# RpiOnOff.net
KiCad netlist of a schematic drawn in EAGLE
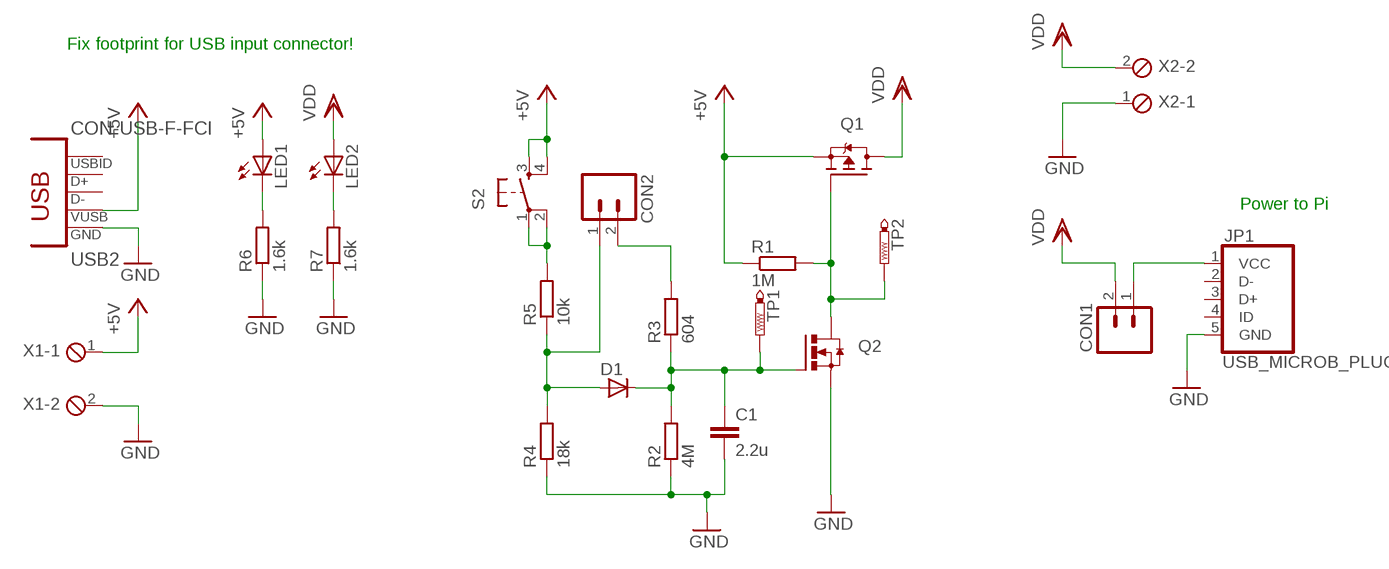
[diagram p0: schematic, sheet 1]

(export (version "E")
  (design (tool "Eeschema 10.0.6"))
  (components
    (comp (ref "C1")
      (value "2.2u")
      (footprint "eagle-import:C0603")
      (libsource (lib "eagle-import") (part "C-EUC0603"))
    )
    (comp (ref "CON1")
      (value "CONNECTOR-1X2[2.54MM]")
      (footprint "eagle-import:CONNECTOR-1X2-2.54MM")
      (libsource (lib "eagle-import") (part "CONNECTOR-1X2[2.54MM]"))
    )
    (comp (ref "CON2")
      (value "CONNECTOR-1X2[2.54MM]")
      (footprint "eagle-import:CONNECTOR-1X2-2.54MM")
      (libsource (lib "eagle-import") (part "CONNECTOR-1X2[2.54MM]"))
    )
    (comp (ref "D1")
      (value "D-A1-C3")
      (footprint "eagle-import:SOT23")
      (libsource (lib "eagle-import") (part "D-A1-C3"))
    )
    (comp (ref "JP1")
      (value "USB_MICROB_PLUG")
      (footprint "eagle-import:CON-USB-MICRO-B-RA-SMT")
      (libsource (lib "eagle-import") (part "USB_MICROB_PLUG"))
    )
    (comp (ref "LED1")
      (value "LEDCHIP-LED0603")
      (footprint "eagle-import:CHIP-LED0603")
      (libsource (lib "eagle-import") (part "LEDCHIP-LED0603"))
    )
    (comp (ref "LED2")
      (value "LEDCHIP-LED0603")
      (footprint "eagle-import:CHIP-LED0603")
      (libsource (lib "eagle-import") (part "LEDCHIP-LED0603"))
    )
    (comp (ref "Q1")
      (value "MOSFET-P-TOSHIBA-SSM3J338R")
      (footprint "eagle-import:SOT23")
      (libsource (lib "eagle-import") (part "MOSFET-P-TOSHIBA-SSM3J338R"))
    )
    (comp (ref "Q2")
      (value "MOSFET-N-SSM3K36MFV")
      (footprint "eagle-import:SOT23")
      (libsource (lib "eagle-import") (part "MOSFET-N-SSM3K36MFV"))
    )
    (comp (ref "R1")
      (value "1M")
      (footprint "eagle-import:R0603")
      (libsource (lib "eagle-import") (part "R-EU_R0603"))
    )
    (comp (ref "R2")
      (value "4M")
      (footprint "eagle-import:R0603")
      (libsource (lib "eagle-import") (part "R-EU_R0603"))
    )
    (comp (ref "R3")
      (value "604")
      (footprint "eagle-import:R0603")
      (libsource (lib "eagle-import") (part "R-EU_R0603"))
    )
    (comp (ref "R4")
      (value "18k")
      (footprint "eagle-import:R0603")
      (libsource (lib "eagle-import") (part "R-EU_R0603"))
    )
    (comp (ref "R5")
      (value "10k")
      (footprint "eagle-import:R0603")
      (libsource (lib "eagle-import") (part "R-EU_R0603"))
    )
    (comp (ref "R6")
      (value "1.6k")
      (footprint "eagle-import:R0603")
      (libsource (lib "eagle-import") (part "R-EU_R0603"))
    )
    (comp (ref "R7")
      (value "1.6k")
      (footprint "eagle-import:R0603")
      (libsource (lib "eagle-import") (part "R-EU_R0603"))
    )
    (comp (ref "S2")
      (value "TACT-4PINCK-PTS810")
      (footprint "eagle-import:CK-PTS810")
      (libsource (lib "eagle-import") (part "TACT-4PINCK-PTS810"))
    )
    (comp (ref "TP1")
      (value "PTR1B1,27")
      (footprint "eagle-import:B1,27")
      (libsource (lib "eagle-import") (part "PTR1B1,27"))
    )
    (comp (ref "TP2")
      (value "PTR1B1,27")
      (footprint "eagle-import:B1,27")
      (libsource (lib "eagle-import") (part "PTR1B1,27"))
    )
    (comp (ref "USB2")
      (value "CON-USB-F-FCI")
      (footprint "eagle-import:AMP-USB-MICROB")
      (libsource (lib "eagle-import") (part "CON-USB-F-FCI"))
    )
    (comp (ref "X1")
      (value "MPT2")
      (footprint "eagle-import:2POL254")
      (libsource (lib "eagle-import") (part "MPT2"))
    )
    (comp (ref "X2")
      (value "MPT2")
      (footprint "eagle-import:2POL254")
      (libsource (lib "eagle-import") (part "MPT2"))
    )
  )
  (nets
    (net (code "1") (name "+5V") (class "Default")
      (node (ref "LED1") (pin "A") (pinfunction "A_A") (pintype "passive"))
      (node (ref "Q1") (pin "2") (pinfunction "S_2") (pintype "passive"))
      (node (ref "R1") (pin "1") (pinfunction "1_1") (pintype "passive"))
      (node (ref "S2") (pin "3") (pinfunction "S_3") (pintype "passive"))
      (node (ref "S2") (pin "4") (pinfunction "S1_4") (pintype "passive"))
      (node (ref "USB2") (pin "1") (pinfunction "VUSB_1") (pintype "bidirectional"))
      (node (ref "X1") (pin "1") (pinfunction "1_1") (pintype "passive"))
    )
    (net (code "2") (name "GND") (class "Default")
      (node (ref "C1") (pin "2") (pinfunction "2_2") (pintype "passive"))
      (node (ref "JP1") (pin "5") (pinfunction "GND_5") (pintype "bidirectional"))
      (node (ref "Q2") (pin "2") (pinfunction "S_2") (pintype "passive"))
      (node (ref "R2") (pin "1") (pinfunction "1_1") (pintype "passive"))
      (node (ref "R4") (pin "1") (pinfunction "1_1") (pintype "passive"))
      (node (ref "R6") (pin "1") (pinfunction "1_1") (pintype "passive"))
      (node (ref "R7") (pin "1") (pinfunction "1_1") (pintype "passive"))
      (node (ref "USB2") (pin "5") (pinfunction "GND_5") (pintype "bidirectional"))
      (node (ref "X1") (pin "2") (pinfunction "1_2") (pintype "passive"))
      (node (ref "X2") (pin "1") (pinfunction "1_1") (pintype "passive"))
    )
    (net (code "3") (name "Net-(CON2-Pad2)") (class "Default")
      (node (ref "CON2") (pin "2") (pinfunction "2_2") (pintype "passive"))
      (node (ref "R3") (pin "2") (pinfunction "2_2") (pintype "passive"))
    )
    (net (code "4") (name "Net-(D1-A)") (class "Default")
      (node (ref "CON2") (pin "1") (pinfunction "1_1") (pintype "passive"))
      (node (ref "D1") (pin "1") (pinfunction "A_1") (pintype "passive"))
      (node (ref "R4") (pin "2") (pinfunction "2_2") (pintype "passive"))
      (node (ref "R5") (pin "1") (pinfunction "1_1") (pintype "passive"))
    )
    (net (code "5") (name "Net-(D1-C)") (class "Default")
      (node (ref "C1") (pin "1") (pinfunction "1_1") (pintype "passive"))
      (node (ref "D1") (pin "3") (pinfunction "C_3") (pintype "passive"))
      (node (ref "Q2") (pin "1") (pinfunction "G_1") (pintype "passive"))
      (node (ref "R2") (pin "2") (pinfunction "2_2") (pintype "passive"))
      (node (ref "R3") (pin "1") (pinfunction "1_1") (pintype "passive"))
      (node (ref "TP1") (pin "TP") (pinfunction "TP_TP") (pintype "input"))
    )
    (net (code "6") (name "Net-(JP1-VCC)") (class "Default")
      (node (ref "CON1") (pin "1") (pinfunction "1_1") (pintype "passive"))
      (node (ref "JP1") (pin "1") (pinfunction "VCC_1") (pintype "bidirectional"))
    )
    (net (code "7") (name "Net-(LED1-PadC)") (class "Default")
      (node (ref "LED1") (pin "C") (pinfunction "C_C") (pintype "passive"))
      (node (ref "R6") (pin "2") (pinfunction "2_2") (pintype "passive"))
    )
    (net (code "8") (name "Net-(LED2-PadC)") (class "Default")
      (node (ref "LED2") (pin "C") (pinfunction "C_C") (pintype "passive"))
      (node (ref "R7") (pin "2") (pinfunction "2_2") (pintype "passive"))
    )
    (net (code "9") (name "Net-(Q1-G)") (class "Default")
      (node (ref "Q1") (pin "1") (pinfunction "G_1") (pintype "passive"))
      (node (ref "Q2") (pin "3") (pinfunction "D_3") (pintype "passive"))
      (node (ref "R1") (pin "2") (pinfunction "2_2") (pintype "passive"))
      (node (ref "TP2") (pin "TP") (pinfunction "TP_TP") (pintype "input"))
    )
    (net (code "10") (name "Net-(S2-P)") (class "Default")
      (node (ref "R5") (pin "2") (pinfunction "2_2") (pintype "passive"))
      (node (ref "S2") (pin "1") (pinfunction "P_1") (pintype "passive"))
      (node (ref "S2") (pin "2") (pinfunction "P1_2") (pintype "passive"))
    )
    (net (code "11") (name "VDD") (class "Default")
      (node (ref "CON1") (pin "2") (pinfunction "2_2") (pintype "passive"))
      (node (ref "LED2") (pin "A") (pinfunction "A_A") (pintype "passive"))
      (node (ref "Q1") (pin "3") (pinfunction "D_3") (pintype "passive"))
      (node (ref "X2") (pin "2") (pinfunction "1_2") (pintype "passive"))
    )
    (net (code "12") (name "unconnected-(JP1-D+-Pad3)") (class "Default")
      (node (ref "JP1") (pin "3") (pinfunction "D+_3") (pintype "bidirectional"))
    )
    (net (code "13") (name "unconnected-(JP1-D--Pad2)") (class "Default")
      (node (ref "JP1") (pin "2") (pinfunction "D-_2") (pintype "bidirectional"))
    )
    (net (code "14") (name "unconnected-(JP1-ID-Pad4)") (class "Default")
      (node (ref "JP1") (pin "4") (pinfunction "ID_4") (pintype "bidirectional"))
    )
    (net (code "15") (name "unconnected-(USB2B-D+-Pad3)") (class "Default")
      (node (ref "USB2") (pin "3") (pinfunction "D+_3") (pintype "bidirectional"))
    )
    (net (code "16") (name "unconnected-(USB2B-D--Pad2)") (class "Default")
      (node (ref "USB2") (pin "2") (pinfunction "D-_2") (pintype "bidirectional"))
    )
    (net (code "17") (name "unconnected-(USB2B-USBID-Pad4)") (class "Default")
      (node (ref "USB2") (pin "4") (pinfunction "USBID_4") (pintype "bidirectional"))
    )
  )
)
